# 485.net
KiCad netlist of a schematic drawn in Altium Designer
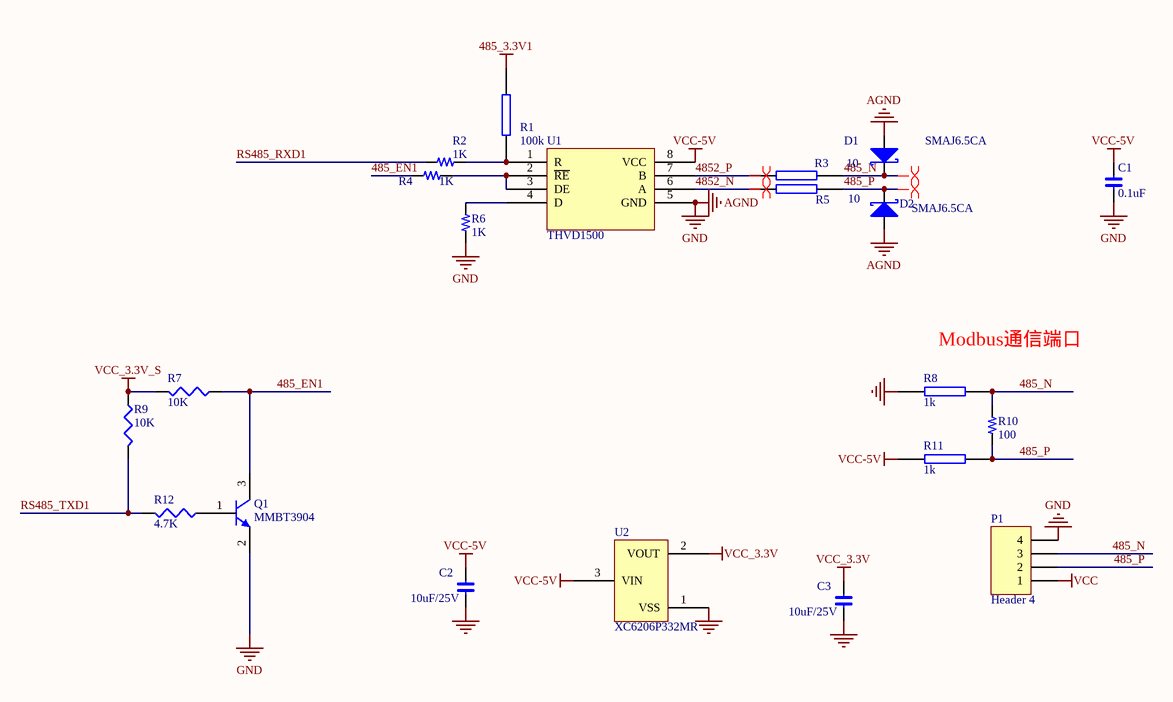
[diagram p0: 485.SchDoc]

(export (version "E")
  (design (tool "Eeschema 10.0.6"))
  (components
    (comp (ref "C1")
      (value "0.1uF")
      (footprint "0603C")
      (description "C")
      (libsource (lib "Schlib_20110825") (part "C"))
    )
    (comp (ref "C2")
      (value "10uF/25V")
      (footprint "0603C")
      (description "C")
      (libsource (lib "Schlib_20110825") (part "C"))
    )
    (comp (ref "C3")
      (value "10uF/25V")
      (footprint "0603C")
      (description "C")
      (libsource (lib "Schlib_20110825") (part "C"))
    )
    (comp (ref "D1")
      (value "SMAJ6.5CA")
      (footprint "SMA")
      (description "Schottky Diode")
      (libsource (lib "*") (part "DIODE S"))
    )
    (comp (ref "D2")
      (value "SMAJ6.5CA")
      (footprint "SMA")
      (description "Schottky Diode")
      (libsource (lib "*") (part "DIODE S"))
    )
    (comp (ref "P1")
      (value "Header 4")
      (footprint "4X2.54MMZ")
      (description "Header, 4-Pin")
      (fields (field (name "PUBLISHER") "Altium Limited"))
      (libsource (lib "Miscellaneous Connectors") (part "Header 4"))
    )
    (comp (ref "Q1") (value "MMBT3904") (footprint "SOT23-3") (libsource (lib "Schlib1") (part "NPN")))
    (comp (ref "R1") (value "100k") (footprint "0603R") (libsource (lib "") (part "RES2_1")))
    (comp (ref "R2") (value "1K") (footprint "0603R") (description "R") (libsource (lib "JRJ_1") (part "R")))
    (comp (ref "R3") (value "10") (footprint "1206R") (libsource (lib "") (part "RES2_1")))
    (comp (ref "R4") (value "1K") (footprint "0603R") (description "R") (libsource (lib "JRJ_1") (part "R")))
    (comp (ref "R5") (value "10") (footprint "1206R") (libsource (lib "") (part "RES2_1")))
    (comp (ref "R6") (value "1K") (footprint "0603R") (description "R") (libsource (lib "JRJ_1") (part "R")))
    (comp (ref "R7")
      (value "10K")
      (footprint "0603R")
      (libsource (lib "ZWLIntegrated_Library") (part "RES1"))
    )
    (comp (ref "R8") (value "1k") (footprint "0603R") (libsource (lib "*") (part "RES2")))
    (comp (ref "R9")
      (value "10K")
      (footprint "0603R")
      (libsource (lib "ZWLIntegrated_Library") (part "RES1"))
    )
    (comp (ref "R10")
      (value "100")
      (footprint "0603R")
      (description "R")
      (libsource (lib "JRJ_1") (part "R"))
    )
    (comp (ref "R11") (value "1k") (footprint "0603R") (libsource (lib "*") (part "RES2")))
    (comp (ref "R12")
      (value "4.7K")
      (footprint "0603R")
      (libsource (lib "ZWLIntegrated_Library") (part "RES1"))
    )
    (comp (ref "U1") (value "THVD1500") (footprint "so-8") (libsource (lib "Schlib1") (part "SN65HVD06D")))
    (comp (ref "U2")
      (value "XC6206P332MR")
      (footprint "SOT23-3")
      (libsource (lib "stm32") (part "XC6206P302MR"))
    )
  )
  (nets
    (net (code "1") (name "/485_EN1") (class "Default")
      (node (ref "Q1") (pin "3") (pinfunction "C_3") (pintype "passive"))
      (node (ref "R4") (pin "2") (pintype "passive"))
      (node (ref "R7") (pin "1") (pinfunction "1_1") (pintype "passive"))
    )
    (net (code "2") (name "/485_N") (class "Default")
      (node (ref "D1") (pin "2") (pinfunction "K_2") (pintype "passive"))
      (node (ref "P1") (pin "3") (pinfunction "3_3") (pintype "passive"))
      (node (ref "R10") (pin "2") (pintype "passive"))
      (node (ref "R3") (pin "1") (pinfunction "1_1") (pintype "passive"))
      (node (ref "R8") (pin "1") (pinfunction "1_1") (pintype "passive"))
    )
    (net (code "3") (name "/485_P") (class "Default")
      (node (ref "D2") (pin "2") (pinfunction "K_2") (pintype "passive"))
      (node (ref "P1") (pin "2") (pinfunction "2_2") (pintype "passive"))
      (node (ref "R10") (pin "1") (pintype "passive"))
      (node (ref "R11") (pin "2") (pinfunction "2_2") (pintype "passive"))
      (node (ref "R5") (pin "1") (pinfunction "1_1") (pintype "passive"))
    )
    (net (code "4") (name "/4852_N") (class "Default")
      (node (ref "R5") (pin "2") (pinfunction "2_2") (pintype "passive"))
      (node (ref "U1") (pin "6") (pinfunction "A_6") (pintype "passive"))
    )
    (net (code "5") (name "/4852_P") (class "Default")
      (node (ref "R3") (pin "2") (pinfunction "2_2") (pintype "passive"))
      (node (ref "U1") (pin "7") (pinfunction "B_7") (pintype "passive"))
    )
    (net (code "6") (name "/RS485_RXD1") (class "Default") (node (ref "R2") (pin "2") (pintype "passive")))
    (net (code "7") (name "/RS485_TXD1") (class "Default")
      (node (ref "R12") (pin "2") (pinfunction "2_2") (pintype "passive"))
      (node (ref "R9") (pin "2") (pinfunction "2_2") (pintype "passive"))
    )
    (net (code "8") (name "485_3.3V1") (class "Default")
      (node (ref "R1") (pin "2") (pinfunction "2_2") (pintype "passive"))
    )
    (net (code "9") (name "AGND") (class "Default")
      (node (ref "C1") (pin "1") (pintype "passive"))
      (node (ref "C2") (pin "1") (pintype "passive"))
      (node (ref "C3") (pin "1") (pintype "passive"))
      (node (ref "D1") (pin "1") (pinfunction "A_1") (pintype "passive"))
      (node (ref "D2") (pin "1") (pinfunction "A_1") (pintype "passive"))
      (node (ref "P1") (pin "4") (pinfunction "4_4") (pintype "passive"))
      (node (ref "Q1") (pin "2") (pinfunction "E_2") (pintype "passive"))
      (node (ref "R6") (pin "2") (pintype "passive"))
      (node (ref "R8") (pin "2") (pinfunction "2_2") (pintype "passive"))
      (node (ref "U1") (pin "5") (pinfunction "GND_5") (pintype "passive"))
      (node (ref "U2") (pin "1") (pinfunction "VSS_1") (pintype "passive"))
    )
    (net (code "10") (name "Net-(Q1-B)") (class "Default")
      (node (ref "Q1") (pin "1") (pinfunction "B_1") (pintype "passive"))
      (node (ref "R12") (pin "1") (pinfunction "1_1") (pintype "passive"))
    )
    (net (code "11") (name "Net-(U1-D)") (class "Default")
      (node (ref "R6") (pin "1") (pintype "passive"))
      (node (ref "U1") (pin "4") (pinfunction "D_4") (pintype "passive"))
    )
    (net (code "12") (name "Net-(U1-DE)") (class "Default")
      (node (ref "R4") (pin "1") (pintype "passive"))
      (node (ref "U1") (pin "2") (pinfunction "~{RE}_2") (pintype "passive"))
      (node (ref "U1") (pin "3") (pinfunction "DE_3") (pintype "passive"))
    )
    (net (code "13") (name "Net-(U1-R)") (class "Default")
      (node (ref "R1") (pin "1") (pinfunction "1_1") (pintype "passive"))
      (node (ref "R2") (pin "1") (pintype "passive"))
      (node (ref "U1") (pin "1") (pinfunction "R_1") (pintype "passive"))
    )
    (net (code "14") (name "VCC") (class "Default")
      (node (ref "P1") (pin "1") (pinfunction "1_1") (pintype "passive"))
    )
    (net (code "15") (name "VCC-5V") (class "Default")
      (node (ref "C1") (pin "2") (pintype "passive"))
      (node (ref "C2") (pin "2") (pintype "passive"))
      (node (ref "R11") (pin "1") (pinfunction "1_1") (pintype "passive"))
      (node (ref "U1") (pin "8") (pinfunction "VCC_8") (pintype "passive"))
      (node (ref "U2") (pin "3") (pinfunction "VIN_3") (pintype "passive"))
    )
    (net (code "16") (name "VCC_3.3V") (class "Default")
      (node (ref "C3") (pin "2") (pintype "passive"))
      (node (ref "U2") (pin "2") (pinfunction "VOUT_2") (pintype "passive"))
    )
    (net (code "17") (name "VCC_3.3V_S") (class "Default")
      (node (ref "R7") (pin "2") (pinfunction "2_2") (pintype "passive"))
      (node (ref "R9") (pin "1") (pinfunction "1_1") (pintype "passive"))
    )
  )
)
